# Adafruit_MPM3610.net
KiCad netlist of a schematic drawn in EAGLE
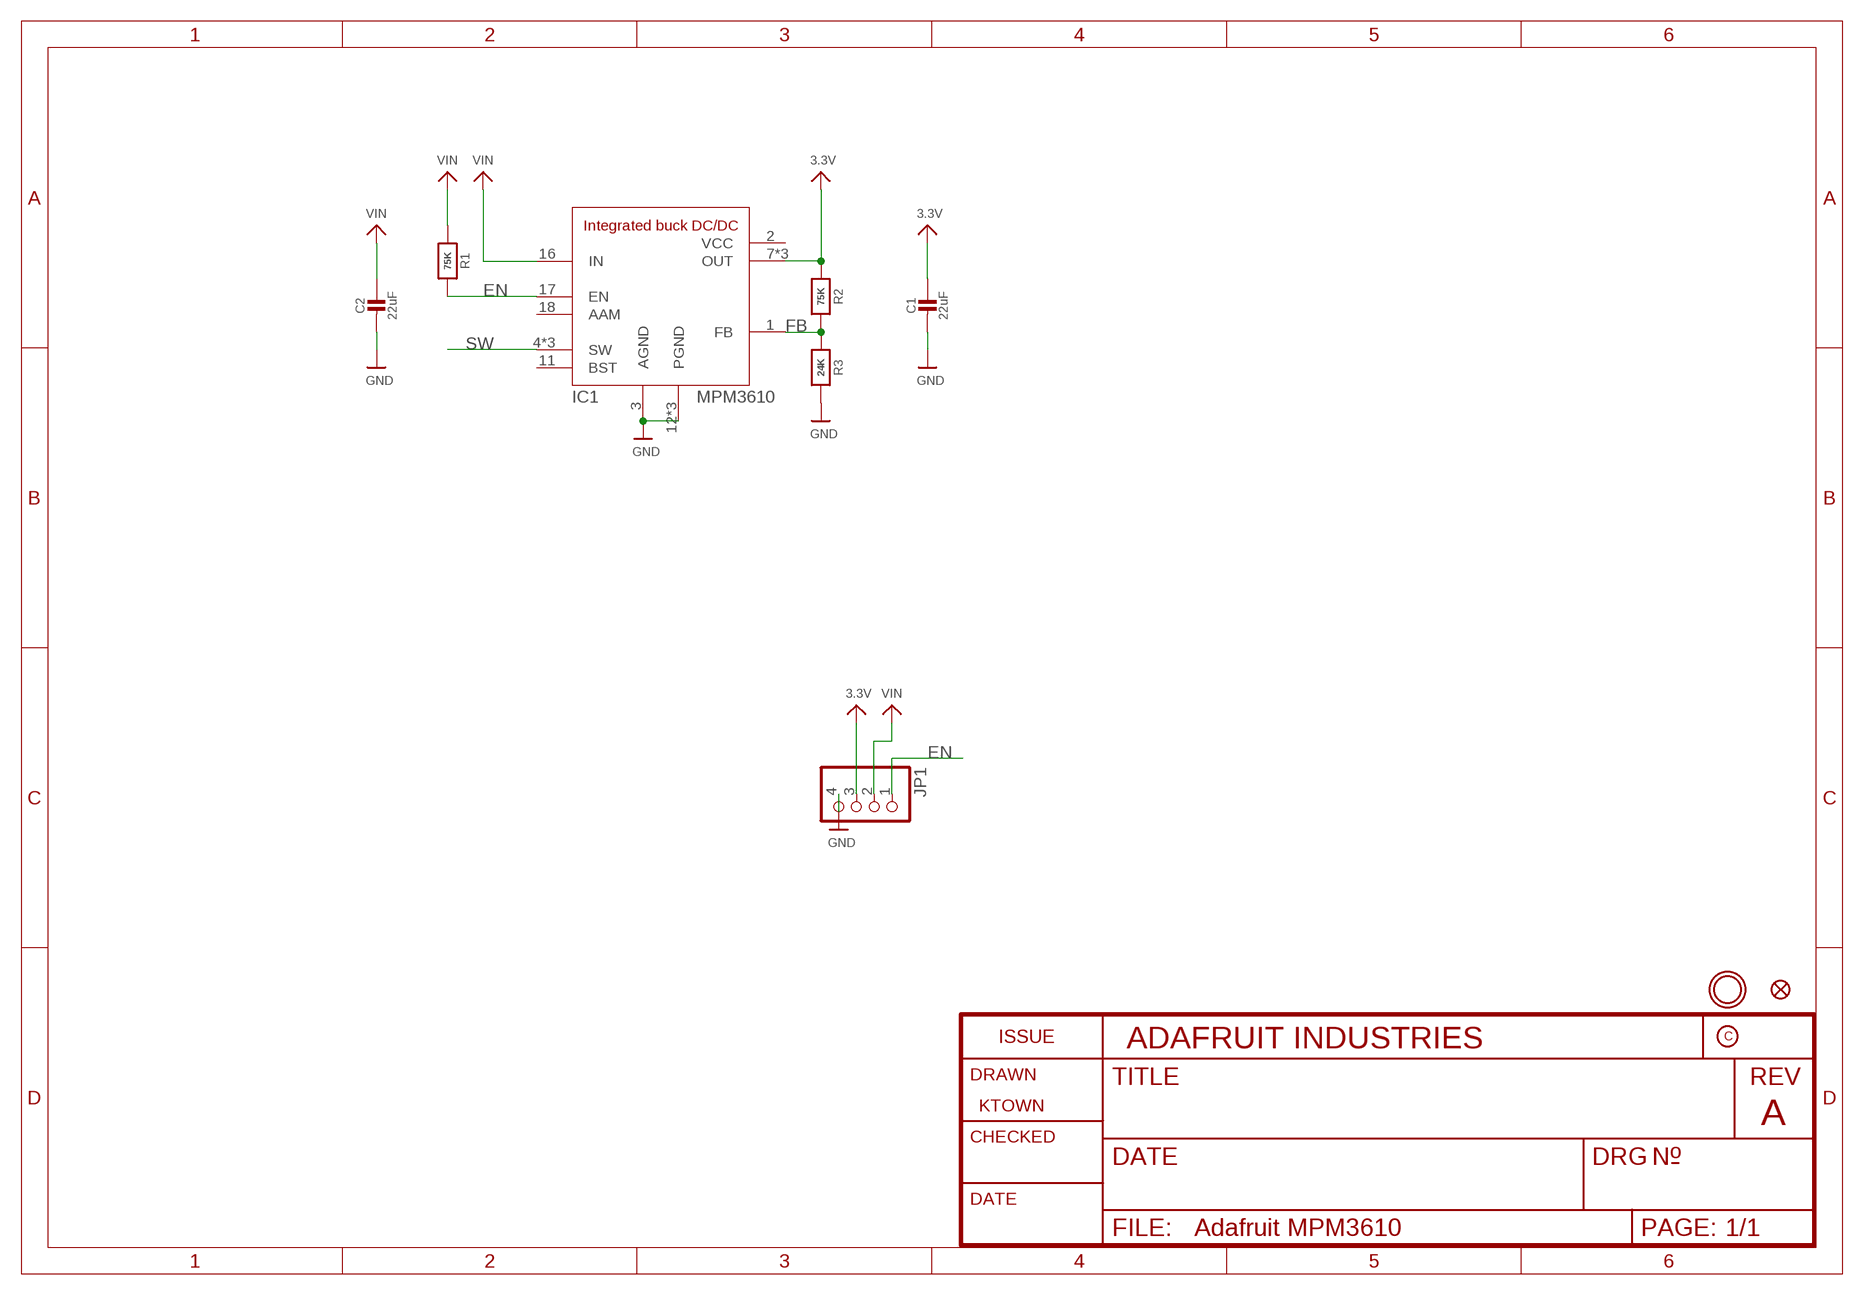
[diagram p0: schematic, sheet 1]

(export (version "E")
  (design (tool "Eeschema 10.0.6"))
  (components
    (comp (ref "C1")
      (value "22uF")
      (footprint "eagle-import:0805-NO")
      (libsource (lib "eagle-import") (part "CAP_CERAMIC0805-NOOUTLINE"))
    )
    (comp (ref "C2")
      (value "22uF")
      (footprint "eagle-import:0805-NO")
      (libsource (lib "eagle-import") (part "CAP_CERAMIC0805-NOOUTLINE"))
    )
    (comp (ref "FID1")
      (value "FIDUCIAL_1MM")
      (footprint "eagle-import:FIDUCIAL_1MM")
      (libsource (lib "eagle-import") (part "FIDUCIAL_1MM"))
    )
    (comp (ref "IC1")
      (value "MPM3610")
      (footprint "eagle-import:MPM3610")
      (libsource (lib "eagle-import") (part "MPM3610"))
    )
    (comp (ref "JP1")
      (value "HEADER-1X4ROUND")
      (footprint "eagle-import:1X04_ROUND")
      (libsource (lib "eagle-import") (part "HEADER-1X4ROUND"))
    )
    (comp (ref "R1")
      (value "75K")
      (footprint "eagle-import:0603-NO")
      (libsource (lib "eagle-import") (part "RESISTOR_0603_NOOUT"))
    )
    (comp (ref "R2")
      (value "75K")
      (footprint "eagle-import:0603-NO")
      (libsource (lib "eagle-import") (part "RESISTOR_0603_NOOUT"))
    )
    (comp (ref "R3")
      (value "24K")
      (footprint "eagle-import:0603-NO")
      (libsource (lib "eagle-import") (part "RESISTOR_0603_NOOUT"))
    )
    (comp (ref "U$9")
      (value "MOUNTINGHOLE2.5")
      (footprint "eagle-import:MOUNTINGHOLE_2.5_PLATED")
      (libsource (lib "eagle-import") (part "MOUNTINGHOLE2.5"))
    )
  )
  (nets
    (net (code "1") (name "/EN") (class "Default")
      (node (ref "IC1") (pin "17") (pinfunction "EN_17") (pintype "input"))
      (node (ref "JP1") (pin "1") (pinfunction "1_1") (pintype "passive"))
      (node (ref "R1") (pin "2") (pinfunction "2_2") (pintype "passive"))
    )
    (net (code "2") (name "/FB") (class "Default")
      (node (ref "IC1") (pin "1") (pinfunction "FB_1") (pintype "input"))
      (node (ref "R2") (pin "2") (pinfunction "2_2") (pintype "passive"))
      (node (ref "R3") (pin "1") (pinfunction "1_1") (pintype "passive"))
    )
    (net (code "3") (name "/SW") (class "Default")
      (node (ref "IC1") (pin "4") (pinfunction "SW_4") (pintype "passive"))
      (node (ref "IC1") (pin "5") (pinfunction "SW_5") (pintype "passive"))
      (node (ref "IC1") (pin "6") (pinfunction "SW_6") (pintype "passive"))
    )
    (net (code "4") (name "/VCC") (class "Default")
      (node (ref "IC1") (pin "2") (pinfunction "VCC_2") (pintype "power_in"))
    )
    (net (code "5") (name "3.3V") (class "Default")
      (node (ref "C1") (pin "1") (pinfunction "1_1") (pintype "passive"))
      (node (ref "IC1") (pin "7") (pinfunction "OUT_7") (pintype "power_in"))
      (node (ref "IC1") (pin "8") (pinfunction "OUT_8") (pintype "power_in"))
      (node (ref "IC1") (pin "9") (pinfunction "OUT_9") (pintype "power_in"))
      (node (ref "JP1") (pin "3") (pinfunction "3_3") (pintype "passive"))
      (node (ref "R2") (pin "1") (pinfunction "1_1") (pintype "passive"))
    )
    (net (code "6") (name "GND") (class "Default")
      (node (ref "C1") (pin "2") (pinfunction "2_2") (pintype "passive"))
      (node (ref "C2") (pin "2") (pinfunction "2_2") (pintype "passive"))
      (node (ref "IC1") (pin "12") (pinfunction "PGND_12") (pintype "power_in"))
      (node (ref "IC1") (pin "13") (pinfunction "PGND_13") (pintype "power_in"))
      (node (ref "IC1") (pin "14") (pinfunction "PGND_14") (pintype "power_in"))
      (node (ref "IC1") (pin "3") (pinfunction "AGND_3") (pintype "power_in"))
      (node (ref "JP1") (pin "4") (pinfunction "4_4") (pintype "passive"))
      (node (ref "R3") (pin "2") (pinfunction "2_2") (pintype "passive"))
    )
    (net (code "7") (name "VIN") (class "Default")
      (node (ref "C2") (pin "1") (pinfunction "1_1") (pintype "passive"))
      (node (ref "IC1") (pin "16") (pinfunction "IN_16") (pintype "power_in"))
      (node (ref "JP1") (pin "2") (pinfunction "2_2") (pintype "passive"))
      (node (ref "R1") (pin "1") (pinfunction "1_1") (pintype "passive"))
    )
    (net (code "8") (name "unconnected-(IC1-AAM-Pad18)") (class "Default")
      (node (ref "IC1") (pin "18") (pinfunction "AAM_18") (pintype "input"))
    )
    (net (code "9") (name "unconnected-(IC1-BST-Pad11)") (class "Default")
      (node (ref "IC1") (pin "11") (pinfunction "BST_11") (pintype "passive"))
    )
  )
)
